# SMPS.net
KiCad netlist of a schematic drawn in Altium Designer
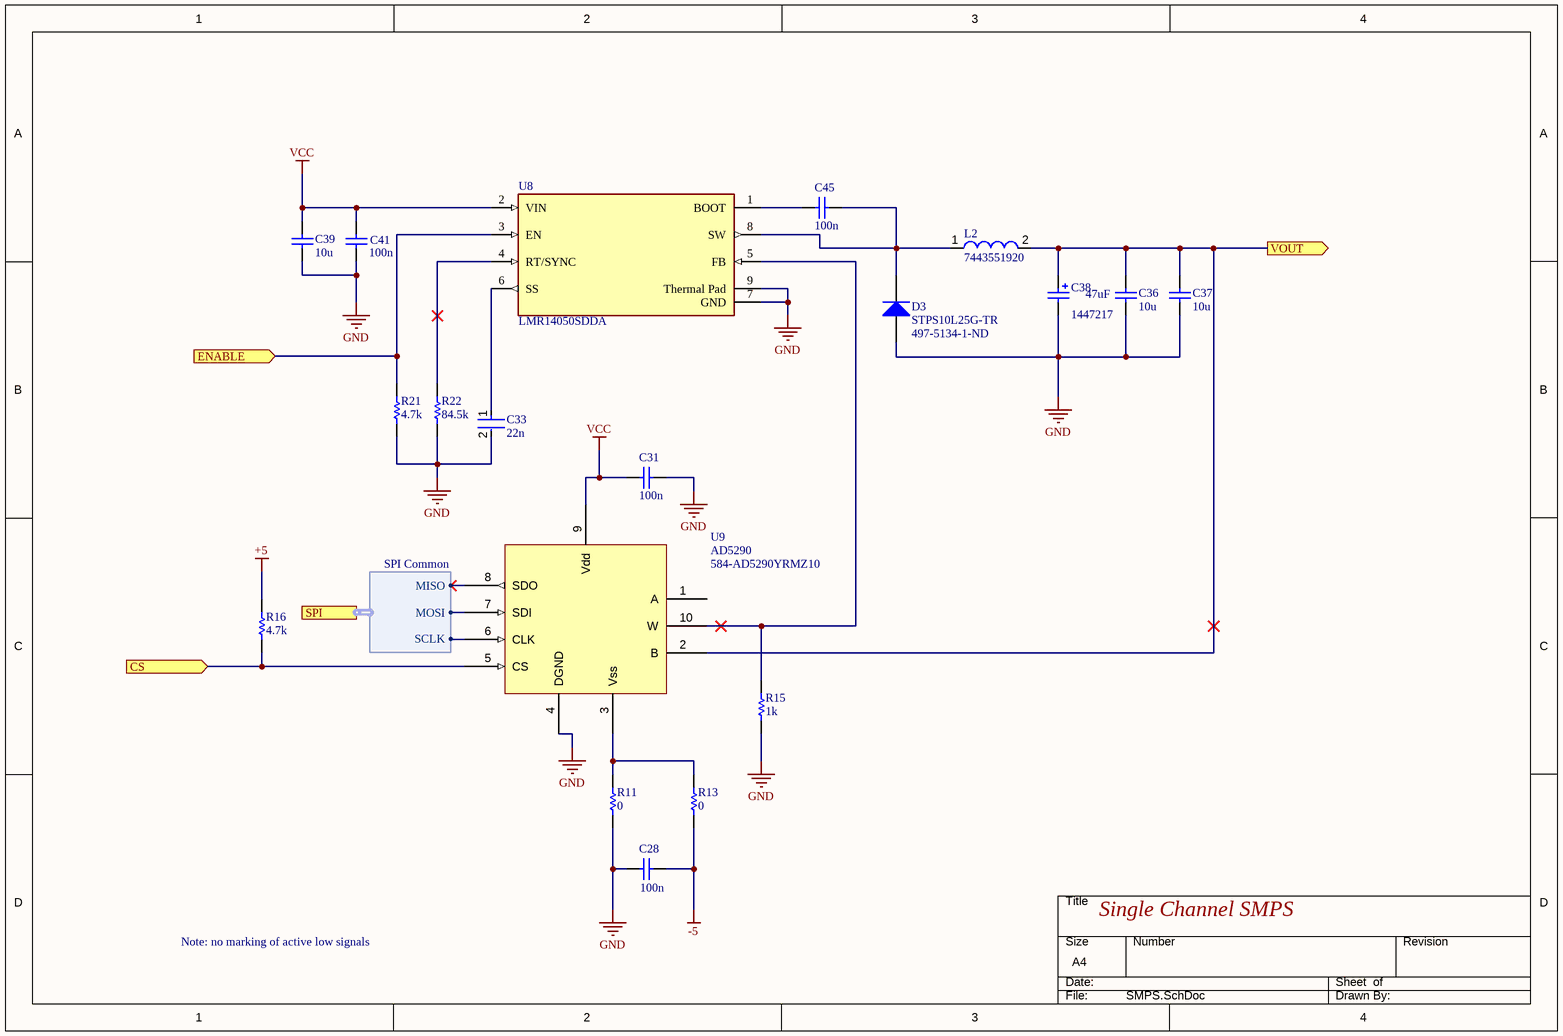
[diagram p0: SMPS.SchDoc]

(export (version "E")
  (design (tool "Eeschema 10.0.6"))
  (components
    (comp (ref "C28")
      (value "100n")
      (footprint "CAPC2013X145X50LL20T25")
      (fields (field (name "MANUFACTURER") "Kemet") (field (name "PART NUMBER") "C0805C104K3RALTU"))
      (libsource (lib "Altium Content Vault") (part "CAP"))
    )
    (comp (ref "C31")
      (value "100n")
      (footprint "CAPC2013X145X50NL20T25")
      (fields (field (name "MANUFACTURER") "Kemet") (field (name "PART NUMBER") "C0805C104K3RALTU"))
      (libsource (lib "Altium Content Vault") (part "CAP"))
    )
    (comp (ref "C33")
      (value "22n")
      (footprint "FP-CC0805-0_85-MFG")
      (description "CAP CER 0.022UF 25V X7R 0805")
      (fields
        (field (name "OCTOPART") "https://octopart.com/cc0805krx7r8bb223-yageo-42522869")
        (field (name "MANUFACTURER PART NUMBER") "CC0805KRX7R8BB223")
      )
      (libsource (lib "Altium Content Vault") (part "11868f565c42a9108669ba33697ecf6"))
    )
    (comp (ref "C36")
      (value "10u")
      (footprint "CAPC3216X180X55LL20T30")
      (fields (field (name "MANUFACTURER") "Taiyo Yuden") (field (name "TOLERANCE") "±10%"))
      (libsource (lib "Altium Content Vault") (part "CAP-NP-2"))
    )
    (comp (ref "C37")
      (value "10u")
      (footprint "CAPC3216X180X55LL20T30")
      (fields (field (name "MANUFACTURER") "Taiyo Yuden") (field (name "TOLERANCE") "±10%"))
      (libsource (lib "Altium Content Vault") (part "CAP-NP-2"))
    )
    (comp (ref "C38")
      (value "T521X476M035ATE030")
      (footprint "7343")
      (description "KEMET - T521X476M035ATE030 - CAP, TANT, POLYMER, 47UF, 35V, CASE X")
      (fields
        (field (name "MANUFACTURER") "KEMET")
        (field (name "CAPACITANCE") "47uF")
        (field (name "TOLERANCE") "20%")
        (field (name "SUPPLIER PART NUMBER 1") "1447217")
      )
      (libsource (lib "PPS Lib") (part "T521X476M035ATE030"))
    )
    (comp (ref "C39")
      (value "10u")
      (footprint "CAPC3216X180X55LL20T30")
      (fields (field (name "MANUFACTURER") "Taiyo Yuden") (field (name "TOLERANCE") "±10%"))
      (libsource (lib "Altium Content Vault") (part "CAP-NP-2"))
    )
    (comp (ref "C41")
      (value "100n")
      (footprint "CAPC2013X145X50LL20T25")
      (fields (field (name "MANUFACTURER") "Kemet") (field (name "PART NUMBER") "C0805C104K3RALTU"))
      (libsource (lib "Altium Content Vault") (part "CAP"))
    )
    (comp (ref "C45")
      (value "100n")
      (footprint "CAPC2013X145X50LL20T25")
      (fields (field (name "MANUFACTURER") "Kemet") (field (name "PART NUMBER") "C0805C104K3RALTU"))
      (libsource (lib "Altium Content Vault") (part "CAP"))
    )
    (comp (ref "D3")
      (value "STPS10L25G-TR")
      (footprint "D2PAK")
      (description "STMICROELECTRONICS   STPS10L25G-TR   DIODE, SCHOTTKY, 10A, 25V, DPAK")
      (fields
        (field (name "MANUFACTURER") "STMicroelectronics")
        (field (name "SUPPLIER PART NUMBER 1") "497-5134-1-ND")
      )
      (libsource (lib "PPS Lib") (part "STPS10L25G-TR"))
    )
    (comp (ref "L2")
      (value "7443551920")
      (footprint "WE-HCI-1365")
      (description "SMD Flat Wire High Current Inductor WE-HCI, L=9.20 µH")
      (libsource (lib "Altium Content Vault") (part "PAS-IND-INDUCTOR-2"))
    )
    (comp (ref "R11")
      (value "0")
      (footprint "RESC2013X70X40NL20T20")
      (description "Chip Resistor, 0 Ohm, +/- 1%, 0.125 W, -55 to 155 degC, 0805 (2012 Metric), RoHS, Tape and Reel")
      (fields (field (name "PARTNUMBER") "ERJ-6GEY0R00V") (field (name "TOLERANCE") "5%"))
      (libsource (lib "Altium Content Vault") (part "RES-2"))
    )
    (comp (ref "R13")
      (value "0")
      (footprint "RESC2013X70X40NL20T20")
      (description "Chip Resistor, 0 Ohm, +/- 1%, 0.125 W, -55 to 155 degC, 0805 (2012 Metric), RoHS, Tape and Reel")
      (fields (field (name "PARTNUMBER") "ERJ-6GEY0R00V") (field (name "TOLERANCE") "5%"))
      (libsource (lib "Altium Content Vault") (part "RES-2"))
    )
    (comp (ref "R15")
      (value "1k")
      (footprint "RESC2013X50X30NL20T20")
      (fields (field (name "PART NUMBER") "CRCW08051K00FKEA") (field (name "MANUFACTURER") "Vishay Dale"))
      (libsource (lib "Altium Content Vault") (part "RES"))
    )
    (comp (ref "R16")
      (value "4.7k")
      (footprint "RESC2013X70X40ML20T20")
      (fields (field (name "MANUFACTURER") "Panasonic") (field (name "PART NUMBER") "ERJ-6GEYJ472V"))
      (libsource (lib "Altium Content Vault") (part "RES"))
    )
    (comp (ref "R21")
      (value "4.7k")
      (footprint "RESC2013X70X40NL20T20")
      (fields (field (name "MANUFACTURER") "Panasonic") (field (name "PART NUMBER") "ERJ-6GEYJ472V"))
      (libsource (lib "Altium Content Vault") (part "RES"))
    )
    (comp (ref "R22")
      (value "84.5k")
      (footprint "RESC2013X60X35NL10T20")
      (fields (field (name "MANUFACTURER") "Yageo") (field (name "PART NUMBER") "RC0805FR-0784K5L"))
      (libsource (lib "Altium Content Vault") (part "RES"))
    )
    (comp (ref "U8")
      (value "LMR14050SDDA")
      (footprint "FP-DDA0008E-IPC_B")
      (description "IC REG BUCK ADJUSTABLE 5A 8SOPWR")
      (libsource (lib "Altium Content Vault") (part "4464e4d661d6cc93f761ec90257100b"))
    )
    (comp (ref "U9")
      (value "AD5290")
      (footprint "MSOP10")
      (description "DIGIPOT 8BIT 10K, SMD, 5290, MSOP10")
      (fields
        (field (name "MANUFACTURER") "Analog Devices")
        (field (name "MANUFACTURER PART NUMBER") "AD5290YRMZ10")
        (field (name "SUPPLIER PART NUMBER 1") "584-AD5290YRMZ10")
      )
      (libsource (lib "PPS Lib") (part "AD5290"))
    )
  )
  (nets
    (net (code "3") (name "+5") (class "Default")
      (node (ref "R16") (pin "2") (pinfunction "2_2") (pintype "passive"))
    )
    (net (code "4") (name "-5") (class "Default")
      (node (ref "C28") (pin "1") (pinfunction "1_1") (pintype "passive"))
      (node (ref "R13") (pin "1") (pinfunction "1_1") (pintype "passive"))
    )
    (net (code "5") (name "/CS") (class "Default")
      (node (ref "R16") (pin "1") (pinfunction "1_1") (pintype "passive"))
      (node (ref "U9") (pin "5") (pinfunction "CS_5") (pintype "input"))
    )
    (net (code "6") (name "/ENABLE") (class "Default")
      (node (ref "R21") (pin "2") (pinfunction "2_2") (pintype "passive"))
      (node (ref "U8") (pin "3") (pinfunction "EN_3") (pintype "input"))
    )
    (net (code "7") (name "/MISO") (class "Default")
      (node (ref "U9") (pin "8") (pinfunction "SDO_8") (pintype "output+no_connect"))
    )
    (net (code "8") (name "/MOSI") (class "Default")
      (node (ref "U9") (pin "7") (pinfunction "SDI_7") (pintype "input"))
    )
    (net (code "9") (name "/SCLK") (class "Default")
      (node (ref "U9") (pin "6") (pinfunction "CLK_6") (pintype "input"))
    )
    (net (code "10") (name "/VOUT") (class "Default")
      (node (ref "C36") (pin "2") (pinfunction "2_2") (pintype "passive"))
      (node (ref "C37") (pin "2") (pinfunction "2_2") (pintype "passive"))
      (node (ref "C38") (pin "1") (pinfunction "1_1") (pintype "passive"))
      (node (ref "L2") (pin "2") (pinfunction "2_2") (pintype "passive"))
      (node (ref "U9") (pin "2") (pinfunction "B_2") (pintype "passive"))
    )
    (net (code "12") (name "GND") (class "Default")
      (node (ref "C28") (pin "2") (pinfunction "2_2") (pintype "passive"))
      (node (ref "C31") (pin "1") (pinfunction "1_1") (pintype "passive"))
      (node (ref "C33") (pin "2") (pinfunction "2_2") (pintype "passive"))
      (node (ref "C36") (pin "1") (pinfunction "1_1") (pintype "passive"))
      (node (ref "C37") (pin "1") (pinfunction "1_1") (pintype "passive"))
      (node (ref "C38") (pin "2") (pinfunction "2_2") (pintype "passive"))
      (node (ref "C39") (pin "1") (pinfunction "1_1") (pintype "passive"))
      (node (ref "C41") (pin "1") (pinfunction "1_1") (pintype "passive"))
      (node (ref "D3") (pin "1") (pinfunction "A_1") (pintype "passive"))
      (node (ref "R11") (pin "1") (pinfunction "1_1") (pintype "passive"))
      (node (ref "R15") (pin "1") (pinfunction "1_1") (pintype "passive"))
      (node (ref "R21") (pin "1") (pinfunction "1_1") (pintype "passive"))
      (node (ref "R22") (pin "1") (pinfunction "1_1") (pintype "passive"))
      (node (ref "U8") (pin "7") (pinfunction "GND_7") (pintype "power_in"))
      (node (ref "U8") (pin "9") (pinfunction "Thermal_Pad_9") (pintype "power_in"))
      (node (ref "U9") (pin "4") (pinfunction "DGND_4") (pintype "power_in"))
    )
    (net (code "13") (name "Net-(D3-K)") (class "Default")
      (node (ref "C45") (pin "1") (pinfunction "1_1") (pintype "passive"))
      (node (ref "D3") (pin "2") (pinfunction "K_2") (pintype "passive"))
      (node (ref "L2") (pin "1") (pinfunction "1_1") (pintype "passive"))
      (node (ref "U8") (pin "8") (pinfunction "SW_8") (pintype "output"))
    )
    (net (code "14") (name "Net-(U8-BOOT)") (class "Default")
      (node (ref "C45") (pin "2") (pinfunction "2_2") (pintype "passive"))
      (node (ref "U8") (pin "1") (pinfunction "BOOT_1") (pintype "passive"))
    )
    (net (code "15") (name "Net-(U8-FB)") (class "Default")
      (node (ref "R15") (pin "2") (pinfunction "2_2") (pintype "passive"))
      (node (ref "U8") (pin "5") (pinfunction "FB_5") (pintype "input"))
      (node (ref "U9") (pin "10") (pinfunction "W_10") (pintype "passive"))
    )
    (net (code "16") (name "Net-(U8-RT{slash}SYNC)") (class "Default")
      (node (ref "R22") (pin "2") (pinfunction "2_2") (pintype "passive"))
      (node (ref "U8") (pin "4") (pinfunction "RT/SYNC_4") (pintype "input"))
    )
    (net (code "17") (name "Net-(U8-SS)") (class "Default")
      (node (ref "C33") (pin "1") (pinfunction "1_1") (pintype "passive"))
      (node (ref "U8") (pin "6") (pinfunction "SS_6") (pintype "output"))
    )
    (net (code "18") (name "Net-(U9-Vss)") (class "Default")
      (node (ref "R11") (pin "2") (pinfunction "2_2") (pintype "passive"))
      (node (ref "R13") (pin "2") (pinfunction "2_2") (pintype "passive"))
      (node (ref "U9") (pin "3") (pinfunction "Vss_3") (pintype "power_in"))
    )
    (net (code "19") (name "VCC") (class "Default")
      (node (ref "C31") (pin "2") (pinfunction "2_2") (pintype "passive"))
      (node (ref "C39") (pin "2") (pinfunction "2_2") (pintype "passive"))
      (node (ref "C41") (pin "2") (pinfunction "2_2") (pintype "passive"))
      (node (ref "U8") (pin "2") (pinfunction "VIN_2") (pintype "input"))
      (node (ref "U9") (pin "9") (pinfunction "Vdd_9") (pintype "power_in"))
    )
    (net (code "20") (name "unconnected-(U9-A-Pad1)") (class "Default")
      (node (ref "U9") (pin "1") (pinfunction "A_1") (pintype "passive"))
    )
  )
)
